# Int_LDOs.net
KiCad netlist of a schematic drawn in Altium Designer
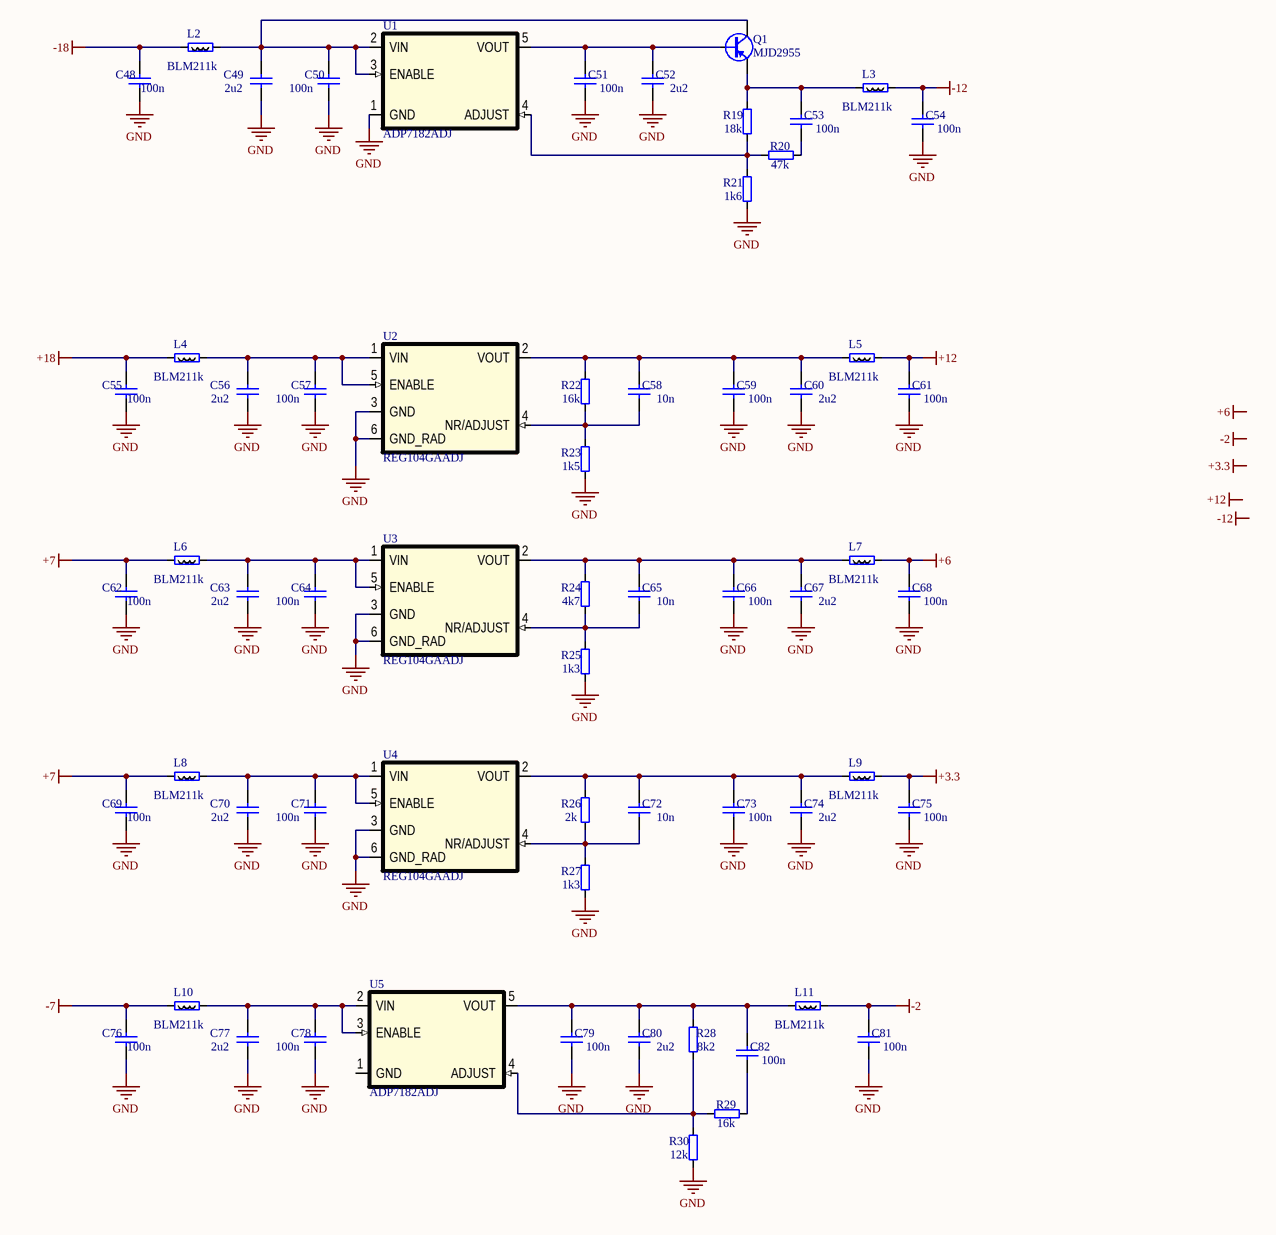
[diagram p0: Int_LDOs.SchDoc]

(export (version "E")
  (design (tool "Eeschema 10.0.6"))
  (components
    (comp (ref "C48") (value "100n") (footprint "0603") (libsource (lib "intS") (part "Capacitor")))
    (comp (ref "C49") (value "2u2") (footprint "0805") (libsource (lib "intS") (part "Capacitor")))
    (comp (ref "C50") (value "100n") (footprint "0603") (libsource (lib "intS") (part "Capacitor")))
    (comp (ref "C51") (value "100n") (footprint "0603") (libsource (lib "intS") (part "Capacitor")))
    (comp (ref "C52") (value "2u2") (footprint "0805") (libsource (lib "intS") (part "Capacitor")))
    (comp (ref "C53") (value "100n") (footprint "0603") (libsource (lib "intS") (part "Capacitor")))
    (comp (ref "C54") (value "100n") (footprint "0603") (libsource (lib "intS") (part "Capacitor")))
    (comp (ref "C55") (value "100n") (footprint "0603") (libsource (lib "intS") (part "Capacitor")))
    (comp (ref "C56") (value "2u2") (footprint "0805") (libsource (lib "intS") (part "Capacitor")))
    (comp (ref "C57") (value "100n") (footprint "0603") (libsource (lib "intS") (part "Capacitor")))
    (comp (ref "C58") (value "10n") (footprint "0603") (libsource (lib "intS") (part "Capacitor")))
    (comp (ref "C59") (value "100n") (footprint "0603") (libsource (lib "intS") (part "Capacitor")))
    (comp (ref "C60") (value "2u2") (footprint "0805") (libsource (lib "intS") (part "Capacitor")))
    (comp (ref "C61") (value "100n") (footprint "0603") (libsource (lib "intS") (part "Capacitor")))
    (comp (ref "C62") (value "100n") (footprint "0603") (libsource (lib "intS") (part "Capacitor")))
    (comp (ref "C63") (value "2u2") (footprint "0805") (libsource (lib "intS") (part "Capacitor")))
    (comp (ref "C64") (value "100n") (footprint "0603") (libsource (lib "intS") (part "Capacitor")))
    (comp (ref "C65") (value "10n") (footprint "0603") (libsource (lib "intS") (part "Capacitor")))
    (comp (ref "C66") (value "100n") (footprint "0603") (libsource (lib "intS") (part "Capacitor")))
    (comp (ref "C67") (value "2u2") (footprint "0805") (libsource (lib "intS") (part "Capacitor")))
    (comp (ref "C68") (value "100n") (footprint "0603") (libsource (lib "intS") (part "Capacitor")))
    (comp (ref "C69") (value "100n") (footprint "0603") (libsource (lib "intS") (part "Capacitor")))
    (comp (ref "C70") (value "2u2") (footprint "0805") (libsource (lib "intS") (part "Capacitor")))
    (comp (ref "C71") (value "100n") (footprint "0603") (libsource (lib "intS") (part "Capacitor")))
    (comp (ref "C72") (value "10n") (footprint "0603") (libsource (lib "intS") (part "Capacitor")))
    (comp (ref "C73") (value "100n") (footprint "0603") (libsource (lib "intS") (part "Capacitor")))
    (comp (ref "C74") (value "2u2") (footprint "0805") (libsource (lib "intS") (part "Capacitor")))
    (comp (ref "C75") (value "100n") (footprint "0603") (libsource (lib "intS") (part "Capacitor")))
    (comp (ref "C76") (value "100n") (footprint "0603") (libsource (lib "intS") (part "Capacitor")))
    (comp (ref "C77") (value "2u2") (footprint "0805") (libsource (lib "intS") (part "Capacitor")))
    (comp (ref "C78") (value "100n") (footprint "0603") (libsource (lib "intS") (part "Capacitor")))
    (comp (ref "C79") (value "100n") (footprint "0603") (libsource (lib "intS") (part "Capacitor")))
    (comp (ref "C80") (value "2u2") (footprint "0805") (libsource (lib "intS") (part "Capacitor")))
    (comp (ref "C81") (value "100n") (footprint "0603") (libsource (lib "intS") (part "Capacitor")))
    (comp (ref "C82") (value "100n") (footprint "0603") (libsource (lib "intS") (part "Capacitor")))
    (comp (ref "L2")
      (value "BLM211k")
      (footprint "0805")
      (description "SMD Ferrite bead 0805")
      (libsource (lib "intS") (part "BLM21"))
    )
    (comp (ref "L3")
      (value "BLM211k")
      (footprint "0805")
      (description "SMD Ferrite bead 0805")
      (libsource (lib "intS") (part "BLM21"))
    )
    (comp (ref "L4")
      (value "BLM211k")
      (footprint "0805")
      (description "SMD Ferrite bead 0805")
      (libsource (lib "intS") (part "BLM21"))
    )
    (comp (ref "L5")
      (value "BLM211k")
      (footprint "0805")
      (description "SMD Ferrite bead 0805")
      (libsource (lib "intS") (part "BLM21"))
    )
    (comp (ref "L6")
      (value "BLM211k")
      (footprint "0805")
      (description "SMD Ferrite bead 0805")
      (libsource (lib "intS") (part "BLM21"))
    )
    (comp (ref "L7")
      (value "BLM211k")
      (footprint "0805")
      (description "SMD Ferrite bead 0805")
      (libsource (lib "intS") (part "BLM21"))
    )
    (comp (ref "L8")
      (value "BLM211k")
      (footprint "0805")
      (description "SMD Ferrite bead 0805")
      (libsource (lib "intS") (part "BLM21"))
    )
    (comp (ref "L9")
      (value "BLM211k")
      (footprint "0805")
      (description "SMD Ferrite bead 0805")
      (libsource (lib "intS") (part "BLM21"))
    )
    (comp (ref "L10")
      (value "BLM211k")
      (footprint "0805")
      (description "SMD Ferrite bead 0805")
      (libsource (lib "intS") (part "BLM21"))
    )
    (comp (ref "L11")
      (value "BLM211k")
      (footprint "0805")
      (description "SMD Ferrite bead 0805")
      (libsource (lib "intS") (part "BLM21"))
    )
    (comp (ref "Q1")
      (value "MJD2955")
      (footprint "DPAK")
      (description "PNP транзистор")
      (fields (field (name "VOLTAGE") "-60V"))
      (libsource (lib "intS") (part "MJD2955"))
    )
    (comp (ref "R19") (value "18k") (footprint "0603") (libsource (lib "intS") (part "Resistor")))
    (comp (ref "R20") (value "47k") (footprint "0603") (libsource (lib "intS") (part "Resistor")))
    (comp (ref "R21") (value "1k6") (footprint "0603") (libsource (lib "intS") (part "Resistor")))
    (comp (ref "R22") (value "16k") (footprint "0603") (libsource (lib "intS") (part "Resistor")))
    (comp (ref "R23") (value "1k5") (footprint "0603") (libsource (lib "intS") (part "Resistor")))
    (comp (ref "R24") (value "4k7") (footprint "0603") (libsource (lib "intS") (part "Resistor")))
    (comp (ref "R25") (value "1k3") (footprint "0603") (libsource (lib "intS") (part "Resistor")))
    (comp (ref "R26") (value "2k") (footprint "0603") (libsource (lib "intS") (part "Resistor")))
    (comp (ref "R27") (value "1k3") (footprint "0603") (libsource (lib "intS") (part "Resistor")))
    (comp (ref "R28") (value "8k2") (footprint "0603") (libsource (lib "intS") (part "Resistor")))
    (comp (ref "R29") (value "16k") (footprint "0603") (libsource (lib "intS") (part "Resistor")))
    (comp (ref "R30") (value "12k") (footprint "0603") (libsource (lib "intS") (part "Resistor")))
    (comp (ref "U1")
      (value "ADP7182ADJ")
      (footprint "SOT23-5")
      (description "Negative LDO Linear stabilizer")
      (libsource (lib "intS") (part "ADP7182"))
    )
    (comp (ref "U2")
      (value "REG104GAADJ")
      (footprint "SOT223_6-127")
      (description "Positive LDO Linear stabilizer")
      (fields (field (name "TOLERANCE") "+-2% Max"))
      (libsource (lib "intS") (part "REG104GA"))
    )
    (comp (ref "U3")
      (value "REG104GAADJ")
      (footprint "SOT223_6-127")
      (description "Positive LDO Linear stabilizer")
      (fields (field (name "TOLERANCE") "+-2% Max"))
      (libsource (lib "intS") (part "REG104GA"))
    )
    (comp (ref "U4")
      (value "REG104GAADJ")
      (footprint "SOT223_6-127")
      (description "Positive LDO Linear stabilizer")
      (fields (field (name "TOLERANCE") "+-2% Max"))
      (libsource (lib "intS") (part "REG104GA"))
    )
    (comp (ref "U5")
      (value "ADP7182ADJ")
      (footprint "SOT23-5")
      (description "Negative LDO Linear stabilizer")
      (libsource (lib "intS") (part "ADP7182"))
    )
  )
  (nets
    (net (code "1") (name "+3.3") (class "Default")
      (node (ref "C75") (pin "2") (pinfunction "2_2") (pintype "passive"))
      (node (ref "L9") (pin "2") (pinfunction "2_2") (pintype "passive"))
    )
    (net (code "2") (name "+6") (class "Default")
      (node (ref "C68") (pin "2") (pinfunction "2_2") (pintype "passive"))
      (node (ref "L7") (pin "2") (pinfunction "2_2") (pintype "passive"))
    )
    (net (code "3") (name "+7") (class "Default")
      (node (ref "C62") (pin "2") (pinfunction "2_2") (pintype "passive"))
      (node (ref "C69") (pin "2") (pinfunction "2_2") (pintype "passive"))
      (node (ref "L6") (pin "1") (pinfunction "1_1") (pintype "passive"))
      (node (ref "L8") (pin "1") (pinfunction "1_1") (pintype "passive"))
    )
    (net (code "4") (name "+12") (class "Default")
      (node (ref "C61") (pin "2") (pinfunction "2_2") (pintype "passive"))
      (node (ref "L5") (pin "2") (pinfunction "2_2") (pintype "passive"))
    )
    (net (code "5") (name "+18") (class "Default")
      (node (ref "C55") (pin "2") (pinfunction "2_2") (pintype "passive"))
      (node (ref "L4") (pin "1") (pinfunction "1_1") (pintype "passive"))
    )
    (net (code "6") (name "-2") (class "Default")
      (node (ref "C81") (pin "2") (pinfunction "2_2") (pintype "passive"))
      (node (ref "L11") (pin "2") (pinfunction "2_2") (pintype "passive"))
    )
    (net (code "7") (name "-7") (class "Default")
      (node (ref "C76") (pin "2") (pinfunction "2_2") (pintype "passive"))
      (node (ref "L10") (pin "1") (pinfunction "1_1") (pintype "passive"))
    )
    (net (code "8") (name "-12") (class "Default")
      (node (ref "C54") (pin "2") (pinfunction "2_2") (pintype "passive"))
      (node (ref "L3") (pin "2") (pinfunction "2_2") (pintype "passive"))
    )
    (net (code "9") (name "-18") (class "Default")
      (node (ref "C48") (pin "2") (pinfunction "2_2") (pintype "passive"))
      (node (ref "L2") (pin "1") (pinfunction "1_1") (pintype "passive"))
    )
    (net (code "10") (name "GND") (class "Default")
      (node (ref "C48") (pin "1") (pinfunction "1_1") (pintype "passive"))
      (node (ref "C49") (pin "1") (pinfunction "1_1") (pintype "passive"))
      (node (ref "C50") (pin "1") (pinfunction "1_1") (pintype "passive"))
      (node (ref "C51") (pin "1") (pinfunction "1_1") (pintype "passive"))
      (node (ref "C52") (pin "1") (pinfunction "1_1") (pintype "passive"))
      (node (ref "C54") (pin "1") (pinfunction "1_1") (pintype "passive"))
      (node (ref "C55") (pin "1") (pinfunction "1_1") (pintype "passive"))
      (node (ref "C56") (pin "1") (pinfunction "1_1") (pintype "passive"))
      (node (ref "C57") (pin "1") (pinfunction "1_1") (pintype "passive"))
      (node (ref "C59") (pin "1") (pinfunction "1_1") (pintype "passive"))
      (node (ref "C60") (pin "1") (pinfunction "1_1") (pintype "passive"))
      (node (ref "C61") (pin "1") (pinfunction "1_1") (pintype "passive"))
      (node (ref "C62") (pin "1") (pinfunction "1_1") (pintype "passive"))
      (node (ref "C63") (pin "1") (pinfunction "1_1") (pintype "passive"))
      (node (ref "C64") (pin "1") (pinfunction "1_1") (pintype "passive"))
      (node (ref "C66") (pin "1") (pinfunction "1_1") (pintype "passive"))
      (node (ref "C67") (pin "1") (pinfunction "1_1") (pintype "passive"))
      (node (ref "C68") (pin "1") (pinfunction "1_1") (pintype "passive"))
      (node (ref "C69") (pin "1") (pinfunction "1_1") (pintype "passive"))
      (node (ref "C70") (pin "1") (pinfunction "1_1") (pintype "passive"))
      (node (ref "C71") (pin "1") (pinfunction "1_1") (pintype "passive"))
      (node (ref "C73") (pin "1") (pinfunction "1_1") (pintype "passive"))
      (node (ref "C74") (pin "1") (pinfunction "1_1") (pintype "passive"))
      (node (ref "C75") (pin "1") (pinfunction "1_1") (pintype "passive"))
      (node (ref "C76") (pin "1") (pinfunction "1_1") (pintype "passive"))
      (node (ref "C77") (pin "1") (pinfunction "1_1") (pintype "passive"))
      (node (ref "C78") (pin "1") (pinfunction "1_1") (pintype "passive"))
      (node (ref "C79") (pin "1") (pinfunction "1_1") (pintype "passive"))
      (node (ref "C80") (pin "1") (pinfunction "1_1") (pintype "passive"))
      (node (ref "C81") (pin "1") (pinfunction "1_1") (pintype "passive"))
      (node (ref "R21") (pin "1") (pinfunction "1_1") (pintype "passive"))
      (node (ref "R23") (pin "1") (pinfunction "1_1") (pintype "passive"))
      (node (ref "R25") (pin "1") (pinfunction "1_1") (pintype "passive"))
      (node (ref "R27") (pin "1") (pinfunction "1_1") (pintype "passive"))
      (node (ref "R30") (pin "1") (pinfunction "1_1") (pintype "passive"))
      (node (ref "U1") (pin "1") (pinfunction "GND_1") (pintype "power_in"))
      (node (ref "U2") (pin "3") (pinfunction "GND_3") (pintype "power_in"))
      (node (ref "U2") (pin "6") (pinfunction "GND_RAD_6") (pintype "power_in"))
      (node (ref "U3") (pin "3") (pinfunction "GND_3") (pintype "power_in"))
      (node (ref "U3") (pin "6") (pinfunction "GND_RAD_6") (pintype "power_in"))
      (node (ref "U4") (pin "3") (pinfunction "GND_3") (pintype "power_in"))
      (node (ref "U4") (pin "6") (pinfunction "GND_RAD_6") (pintype "power_in"))
    )
    (net (code "11") (name "Net-(C53-Pad1)") (class "Default")
      (node (ref "C53") (pin "1") (pinfunction "1_1") (pintype "passive"))
      (node (ref "R20") (pin "2") (pinfunction "2_2") (pintype "passive"))
    )
    (net (code "12") (name "Net-(C82-Pad1)") (class "Default")
      (node (ref "C82") (pin "1") (pinfunction "1_1") (pintype "passive"))
      (node (ref "R29") (pin "2") (pinfunction "2_2") (pintype "passive"))
    )
    (net (code "13") (name "Net-(Q1-B)") (class "Default")
      (node (ref "C51") (pin "2") (pinfunction "2_2") (pintype "passive"))
      (node (ref "C52") (pin "2") (pinfunction "2_2") (pintype "passive"))
      (node (ref "Q1") (pin "1") (pinfunction "B_1") (pintype "passive"))
      (node (ref "U1") (pin "5") (pinfunction "VOUT_5") (pintype "power_in"))
    )
    (net (code "14") (name "Net-(Q1-C)") (class "Default")
      (node (ref "C49") (pin "2") (pinfunction "2_2") (pintype "passive"))
      (node (ref "C50") (pin "2") (pinfunction "2_2") (pintype "passive"))
      (node (ref "L2") (pin "2") (pinfunction "2_2") (pintype "passive"))
      (node (ref "Q1") (pin "3") (pinfunction "C_3") (pintype "passive"))
      (node (ref "U1") (pin "2") (pinfunction "VIN_2") (pintype "power_in"))
      (node (ref "U1") (pin "3") (pinfunction "ENABLE_3") (pintype "input"))
    )
    (net (code "15") (name "Net-(Q1-E)") (class "Default")
      (node (ref "C53") (pin "2") (pinfunction "2_2") (pintype "passive"))
      (node (ref "L3") (pin "1") (pinfunction "1_1") (pintype "passive"))
      (node (ref "Q1") (pin "2") (pinfunction "E_2") (pintype "passive"))
      (node (ref "R19") (pin "2") (pinfunction "2_2") (pintype "passive"))
    )
    (net (code "16") (name "Net-(U1-ADJUST)") (class "Default")
      (node (ref "R19") (pin "1") (pinfunction "1_1") (pintype "passive"))
      (node (ref "R20") (pin "1") (pinfunction "1_1") (pintype "passive"))
      (node (ref "R21") (pin "2") (pinfunction "2_2") (pintype "passive"))
      (node (ref "U1") (pin "4") (pinfunction "ADJUST_4") (pintype "input"))
    )
    (net (code "17") (name "Net-(U2-ENABLE)") (class "Default")
      (node (ref "C56") (pin "2") (pinfunction "2_2") (pintype "passive"))
      (node (ref "C57") (pin "2") (pinfunction "2_2") (pintype "passive"))
      (node (ref "L4") (pin "2") (pinfunction "2_2") (pintype "passive"))
      (node (ref "U2") (pin "1") (pinfunction "VIN_1") (pintype "power_in"))
      (node (ref "U2") (pin "5") (pinfunction "ENABLE_5") (pintype "input"))
    )
    (net (code "18") (name "Net-(U2-NR{slash}ADJUST)") (class "Default")
      (node (ref "C58") (pin "1") (pinfunction "1_1") (pintype "passive"))
      (node (ref "R22") (pin "1") (pinfunction "1_1") (pintype "passive"))
      (node (ref "R23") (pin "2") (pinfunction "2_2") (pintype "passive"))
      (node (ref "U2") (pin "4") (pinfunction "NR/ADJUST_4") (pintype "input"))
    )
    (net (code "19") (name "Net-(U2-VOUT)") (class "Default")
      (node (ref "C58") (pin "2") (pinfunction "2_2") (pintype "passive"))
      (node (ref "C59") (pin "2") (pinfunction "2_2") (pintype "passive"))
      (node (ref "C60") (pin "2") (pinfunction "2_2") (pintype "passive"))
      (node (ref "L5") (pin "1") (pinfunction "1_1") (pintype "passive"))
      (node (ref "R22") (pin "2") (pinfunction "2_2") (pintype "passive"))
      (node (ref "U2") (pin "2") (pinfunction "VOUT_2") (pintype "power_in"))
    )
    (net (code "20") (name "Net-(U3-ENABLE)") (class "Default")
      (node (ref "C63") (pin "2") (pinfunction "2_2") (pintype "passive"))
      (node (ref "C64") (pin "2") (pinfunction "2_2") (pintype "passive"))
      (node (ref "L6") (pin "2") (pinfunction "2_2") (pintype "passive"))
      (node (ref "U3") (pin "1") (pinfunction "VIN_1") (pintype "power_in"))
      (node (ref "U3") (pin "5") (pinfunction "ENABLE_5") (pintype "input"))
    )
    (net (code "21") (name "Net-(U3-NR{slash}ADJUST)") (class "Default")
      (node (ref "C65") (pin "1") (pinfunction "1_1") (pintype "passive"))
      (node (ref "R24") (pin "1") (pinfunction "1_1") (pintype "passive"))
      (node (ref "R25") (pin "2") (pinfunction "2_2") (pintype "passive"))
      (node (ref "U3") (pin "4") (pinfunction "NR/ADJUST_4") (pintype "input"))
    )
    (net (code "22") (name "Net-(U3-VOUT)") (class "Default")
      (node (ref "C65") (pin "2") (pinfunction "2_2") (pintype "passive"))
      (node (ref "C66") (pin "2") (pinfunction "2_2") (pintype "passive"))
      (node (ref "C67") (pin "2") (pinfunction "2_2") (pintype "passive"))
      (node (ref "L7") (pin "1") (pinfunction "1_1") (pintype "passive"))
      (node (ref "R24") (pin "2") (pinfunction "2_2") (pintype "passive"))
      (node (ref "U3") (pin "2") (pinfunction "VOUT_2") (pintype "power_in"))
    )
    (net (code "23") (name "Net-(U4-ENABLE)") (class "Default")
      (node (ref "C70") (pin "2") (pinfunction "2_2") (pintype "passive"))
      (node (ref "C71") (pin "2") (pinfunction "2_2") (pintype "passive"))
      (node (ref "L8") (pin "2") (pinfunction "2_2") (pintype "passive"))
      (node (ref "U4") (pin "1") (pinfunction "VIN_1") (pintype "power_in"))
      (node (ref "U4") (pin "5") (pinfunction "ENABLE_5") (pintype "input"))
    )
    (net (code "24") (name "Net-(U4-NR{slash}ADJUST)") (class "Default")
      (node (ref "C72") (pin "1") (pinfunction "1_1") (pintype "passive"))
      (node (ref "R26") (pin "1") (pinfunction "1_1") (pintype "passive"))
      (node (ref "R27") (pin "2") (pinfunction "2_2") (pintype "passive"))
      (node (ref "U4") (pin "4") (pinfunction "NR/ADJUST_4") (pintype "input"))
    )
    (net (code "25") (name "Net-(U4-VOUT)") (class "Default")
      (node (ref "C72") (pin "2") (pinfunction "2_2") (pintype "passive"))
      (node (ref "C73") (pin "2") (pinfunction "2_2") (pintype "passive"))
      (node (ref "C74") (pin "2") (pinfunction "2_2") (pintype "passive"))
      (node (ref "L9") (pin "1") (pinfunction "1_1") (pintype "passive"))
      (node (ref "R26") (pin "2") (pinfunction "2_2") (pintype "passive"))
      (node (ref "U4") (pin "2") (pinfunction "VOUT_2") (pintype "power_in"))
    )
    (net (code "26") (name "Net-(U5-ADJUST)") (class "Default")
      (node (ref "R28") (pin "1") (pinfunction "1_1") (pintype "passive"))
      (node (ref "R29") (pin "1") (pinfunction "1_1") (pintype "passive"))
      (node (ref "R30") (pin "2") (pinfunction "2_2") (pintype "passive"))
      (node (ref "U5") (pin "4") (pinfunction "ADJUST_4") (pintype "input"))
    )
    (net (code "27") (name "Net-(U5-ENABLE)") (class "Default")
      (node (ref "C77") (pin "2") (pinfunction "2_2") (pintype "passive"))
      (node (ref "C78") (pin "2") (pinfunction "2_2") (pintype "passive"))
      (node (ref "L10") (pin "2") (pinfunction "2_2") (pintype "passive"))
      (node (ref "U5") (pin "2") (pinfunction "VIN_2") (pintype "power_in"))
      (node (ref "U5") (pin "3") (pinfunction "ENABLE_3") (pintype "input"))
    )
    (net (code "28") (name "Net-(U5-VOUT)") (class "Default")
      (node (ref "C79") (pin "2") (pinfunction "2_2") (pintype "passive"))
      (node (ref "C80") (pin "2") (pinfunction "2_2") (pintype "passive"))
      (node (ref "C82") (pin "2") (pinfunction "2_2") (pintype "passive"))
      (node (ref "L11") (pin "1") (pinfunction "1_1") (pintype "passive"))
      (node (ref "R28") (pin "2") (pinfunction "2_2") (pintype "passive"))
      (node (ref "U5") (pin "5") (pinfunction "VOUT_5") (pintype "power_in"))
    )
    (net (code "29") (name "unconnected-(U5-GND-Pad1)") (class "Default")
      (node (ref "U5") (pin "1") (pinfunction "GND_1") (pintype "power_in"))
    )
  )
)
